# high-side-switch.net
KiCad netlist of a schematic drawn in EAGLE
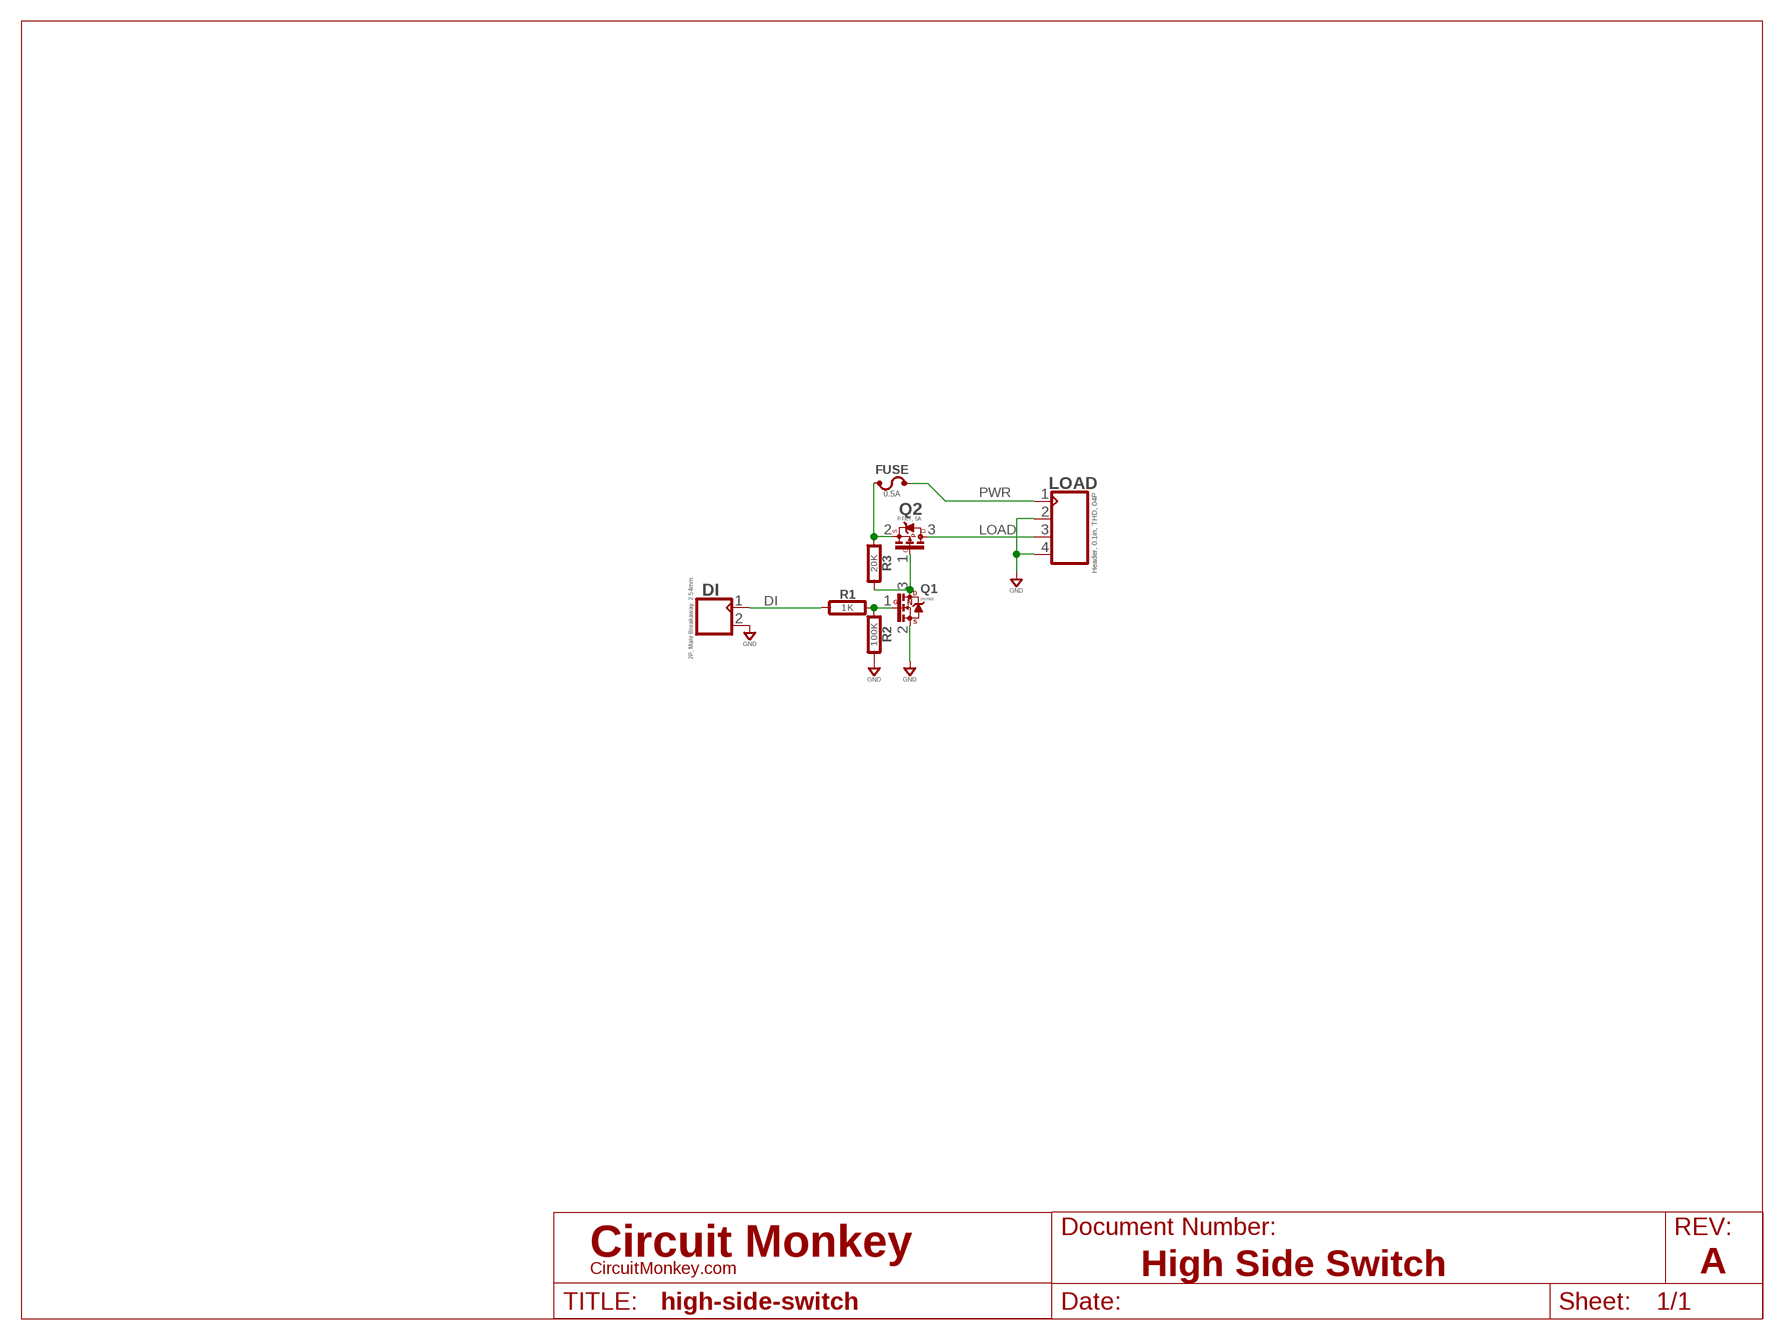
[diagram p0: schematic, sheet 1]

(export (version "E")
  (design (tool "Eeschema 10.0.6"))
  (components
    (comp (ref "DI")
      (value "2P, Male Breakaway, 2.54mm")
      (footprint "eagle-import:MA02X1-VT-THD")
      (libsource (lib "eagle-import") (part "CON_02X1-2.54MM-THD-VT"))
    )
    (comp (ref "FUSE")
      (value "0.5A")
      (footprint "eagle-import:BOURNS-MF-MSMF")
      (fields (field (name "MFR") "BOURNS") (field (name "MPN") "MF-MSMF*"))
      (libsource (lib "eagle-import") (part "FUSEBOURNS-MF-MSMF"))
    )
    (comp (ref "LOAD")
      (value "Header, 0.1in, THD, 04P")
      (footprint "eagle-import:MA04X1-VT-THD")
      (fields (field (name "MFR") "Molex") (field (name "MPN") "022284043"))
      (libsource (lib "eagle-import") (part "CON_04X1-THD-VT"))
    )
    (comp (ref "Q1")
      (value "2N7002")
      (footprint "eagle-import:SOT-23")
      (libsource (lib "eagle-import") (part "N-FET_2N7002"))
    )
    (comp (ref "Q2")
      (value "P-FET, 5A")
      (footprint "eagle-import:SOT-23")
      (fields (field (name "MFR") "Siliconix") (field (name "MPN") "SI2347DS"))
      (libsource (lib "eagle-import") (part "P-FETSOT-23-5A"))
    )
    (comp (ref "R1")
      (value "1K")
      (footprint "eagle-import:0603-RES")
      (libsource (lib "eagle-import") (part "RESISTOR0603"))
    )
    (comp (ref "R2")
      (value "100K")
      (footprint "eagle-import:0603-RES")
      (libsource (lib "eagle-import") (part "RESISTOR0603"))
    )
    (comp (ref "R3")
      (value "20K")
      (footprint "eagle-import:0603-RES")
      (libsource (lib "eagle-import") (part "RESISTOR0603"))
    )
  )
  (nets
    (net (code "1") (name "/DI") (class "Default")
      (node (ref "DI") (pin "1") (pinfunction "1_1") (pintype "passive"))
      (node (ref "R1") (pin "1") (pinfunction "1_1") (pintype "passive"))
    )
    (net (code "2") (name "/LOAD") (class "Default")
      (node (ref "LOAD") (pin "3") (pinfunction "3_3") (pintype "passive"))
      (node (ref "Q2") (pin "3") (pinfunction "D_3") (pintype "bidirectional"))
    )
    (net (code "3") (name "/PWR") (class "Default")
      (node (ref "FUSE") (pin "1") (pinfunction "1_1") (pintype "bidirectional"))
      (node (ref "LOAD") (pin "1") (pinfunction "1_1") (pintype "passive"))
    )
    (net (code "4") (name "GND") (class "Default")
      (node (ref "DI") (pin "2") (pinfunction "2_2") (pintype "passive"))
      (node (ref "LOAD") (pin "2") (pinfunction "2_2") (pintype "passive"))
      (node (ref "LOAD") (pin "4") (pinfunction "4_4") (pintype "passive"))
      (node (ref "Q1") (pin "2") (pinfunction "S_2") (pintype "bidirectional"))
      (node (ref "R2") (pin "2") (pinfunction "2_2") (pintype "passive"))
    )
    (net (code "5") (name "Net-(Q1-D)") (class "Default")
      (node (ref "Q1") (pin "3") (pinfunction "D_3") (pintype "bidirectional"))
      (node (ref "Q2") (pin "1") (pinfunction "G_1") (pintype "bidirectional"))
      (node (ref "R3") (pin "2") (pinfunction "2_2") (pintype "passive"))
    )
    (net (code "6") (name "Net-(Q1-G)") (class "Default")
      (node (ref "Q1") (pin "1") (pinfunction "G_1") (pintype "bidirectional"))
      (node (ref "R1") (pin "2") (pinfunction "2_2") (pintype "passive"))
      (node (ref "R2") (pin "1") (pinfunction "1_1") (pintype "passive"))
    )
    (net (code "7") (name "Net-(Q2-S)") (class "Default")
      (node (ref "FUSE") (pin "2") (pinfunction "2_2") (pintype "bidirectional"))
      (node (ref "Q2") (pin "2") (pinfunction "S_2") (pintype "bidirectional"))
      (node (ref "R3") (pin "1") (pinfunction "1_1") (pintype "passive"))
    )
  )
)
